# MC21R01_Power.net
KiCad netlist of a schematic drawn in Altium Designer
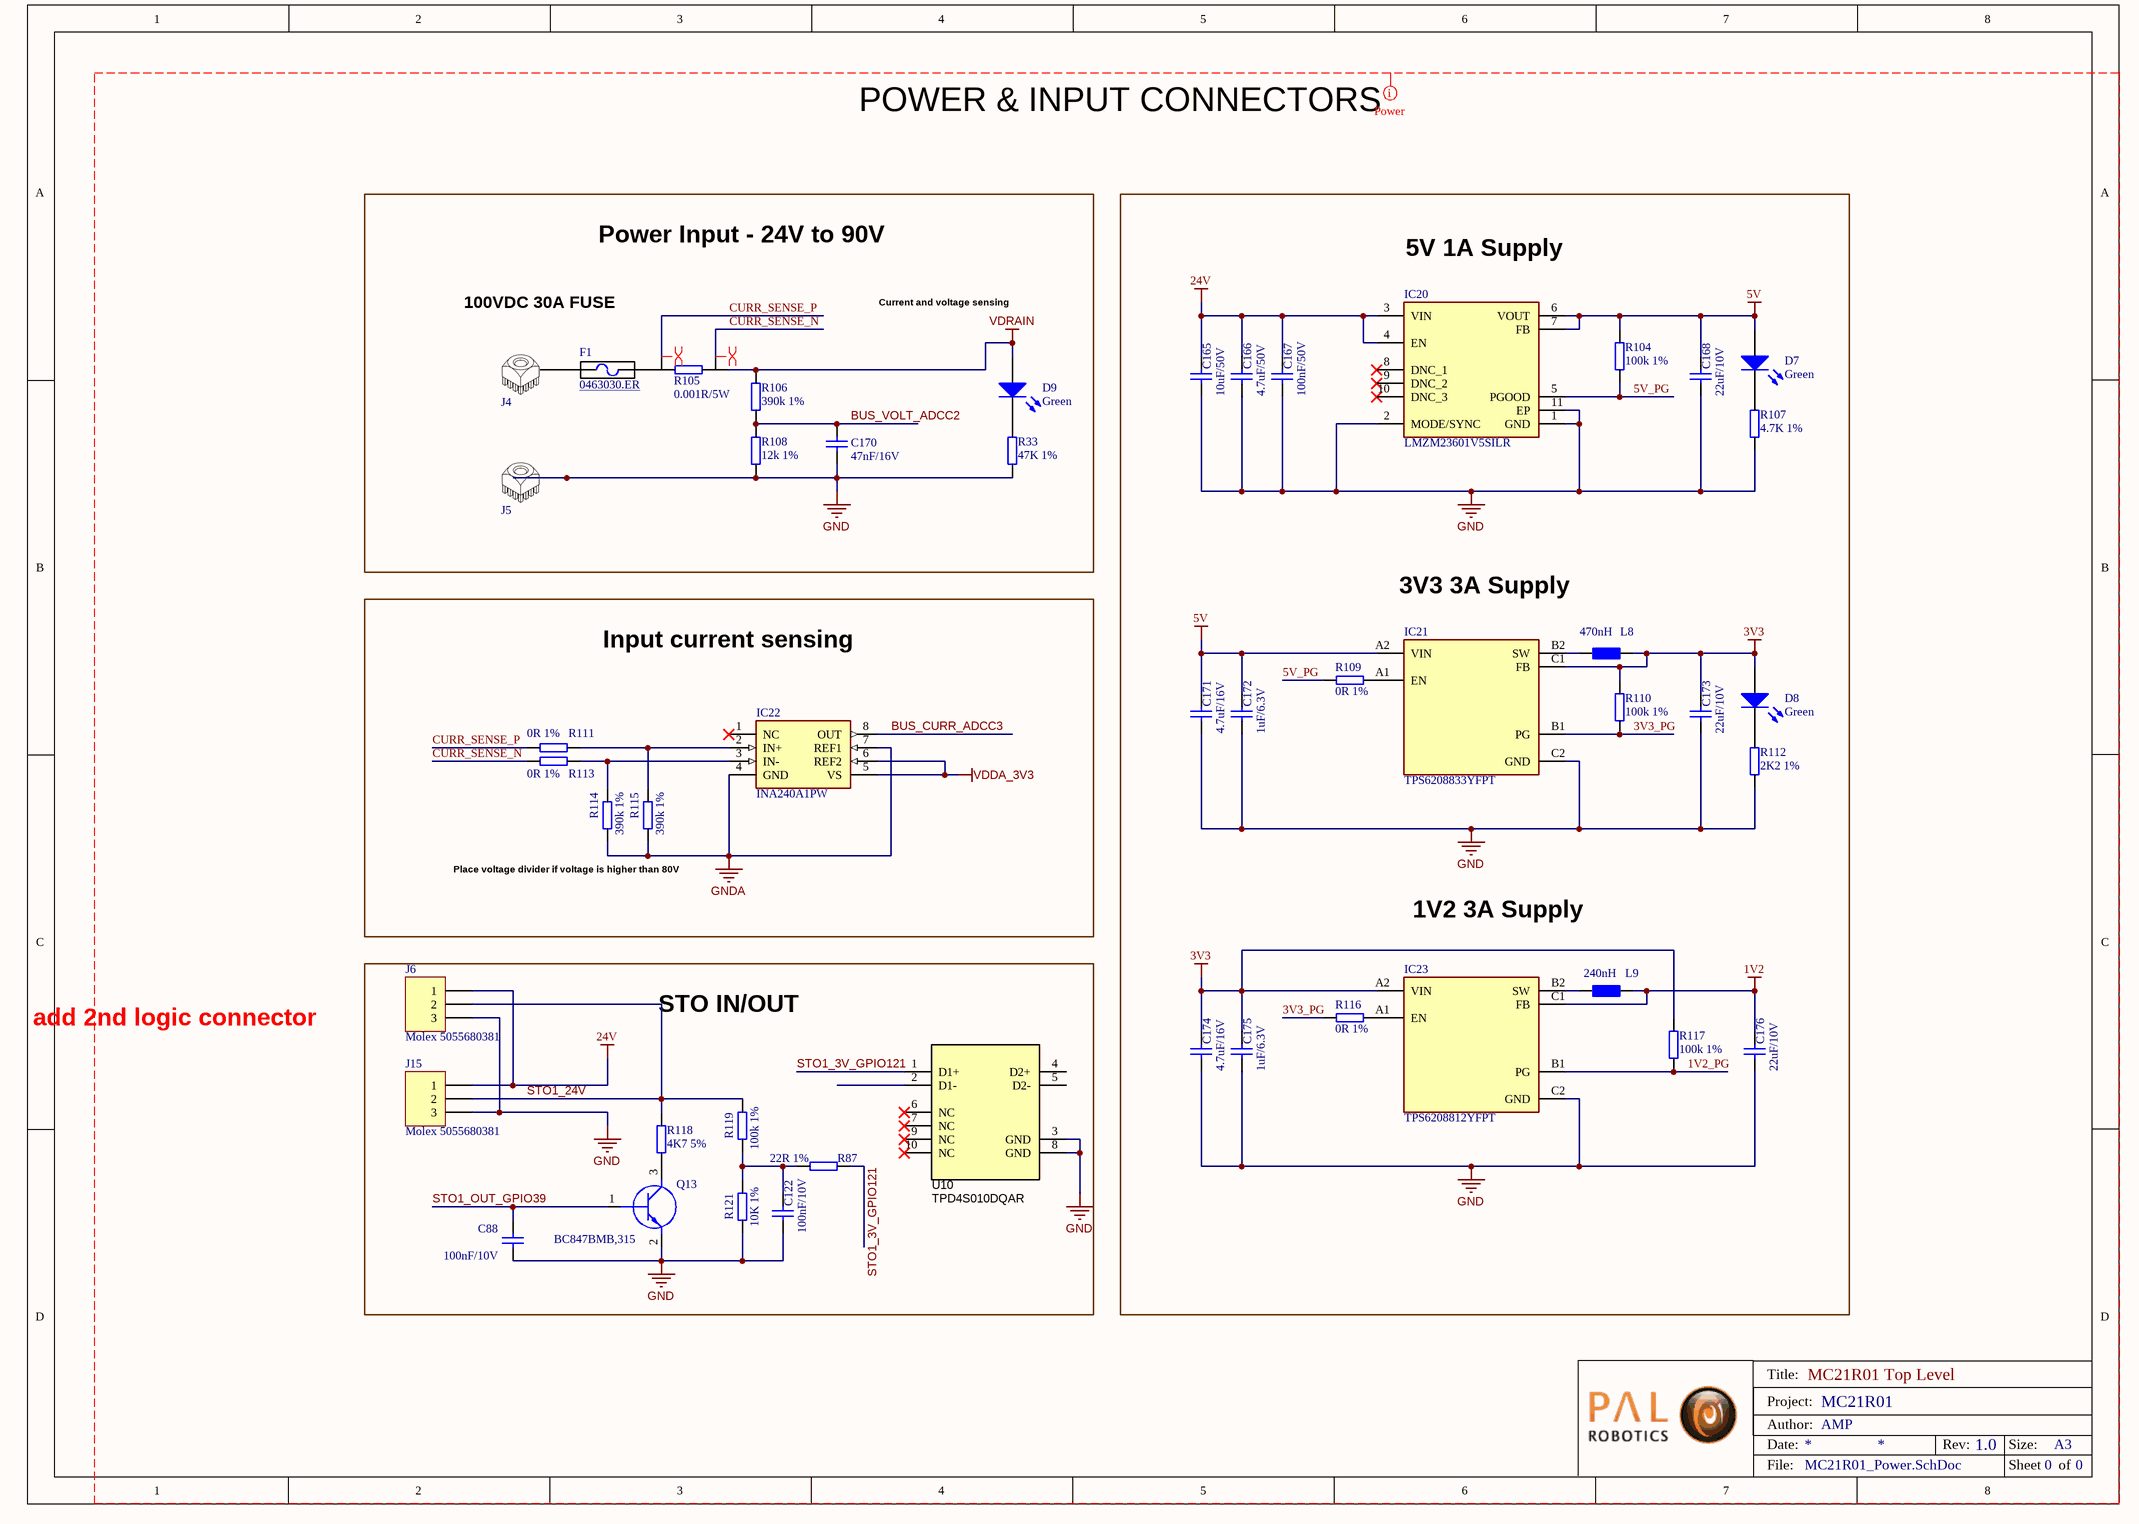
[diagram p0: MC21R01_Power.SchDoc]

(export (version "E")
  (design (tool "Eeschema 10.0.6"))
  (components
    (comp (ref "C88")
      (value "100nF/10V")
      (footprint "PAL_Capacitors:0402 SMD Capacitor")
      (description "100nF/10V 0402 20% Tolerance X5R Multilayer Ceramic Chip Capacitor")
      (fields (field (name "Comment") "100nF/10V 0402 20% X5R"))
      (libsource (lib "PAL_Capacitors") (part "100nF/10V 0402 20% X5R"))
    )
    (comp (ref "C122")
      (value "100nF/10V")
      (footprint "PAL_Capacitors:0402 SMD Capacitor")
      (description "100nF/10V 0402 20% Tolerance X5R Multilayer Ceramic Chip Capacitor")
      (fields (field (name "Comment") "100nF/10V 0402 20% X5R"))
      (libsource (lib "PAL_Capacitors") (part "100nF/10V 0402 20% X5R"))
    )
    (comp (ref "C165")
      (value "10uF/50V")
      (footprint "PAL_Capacitors:1206 SMD Capacitor")
      (description "10 uF 50 V 1206 ±10% Tolerance X5R Multilayer Ceramic Chip Capacitor")
      (fields (field (name "Comment") "10uf/50V 1206 10% X5R"))
      (libsource (lib "PAL_Capacitors") (part "10uF/50V 1206 10% X5R"))
    )
    (comp (ref "C166")
      (value "4.7uF/50V")
      (footprint "PAL_Capacitors:0805 SMD capacitor")
      (description "4.7uF 50 V 0805 ±10% Tolerance X5R Multilayer Ceramic Chip Capacitor")
      (fields (field (name "Comment") "4.7uf/50V 0805 10% X5R"))
      (libsource (lib "PAL_Capacitors") (part "4.7uF/50V 0805 10% X5R"))
    )
    (comp (ref "C167")
      (value "100nF/50V")
      (footprint "PAL_Capacitors:0603 SMD capacitor")
      (description "100 nF 50 V 0603  ±10% Tolerance X7R Multilayer Ceramic Chip Capacitor")
      (fields (field (name "Comment") "100nF/50V 0603 10% X7R"))
      (libsource (lib "PAL_Capacitors") (part "100nF/50V 0603 10% X7R"))
    )
    (comp (ref "C168")
      (value "22uF/10V")
      (footprint "PAL_Capacitors:0603 SMD capacitor")
      (description "22 uF 10 V 0603 ±20% Tolerance X5R Multilayer Ceramic Chip Capacitor")
      (fields (field (name "Comment") "22uF/10V 0603 20% X5R"))
      (libsource (lib "PAL_Capacitors") (part "22uF/10V 0603 20% X5R"))
    )
    (comp (ref "C170")
      (value "47nF/16V")
      (footprint "PAL_Capacitors:0402 SMD Capacitor")
      (description "47nF/16V 0402 10% Tolerance X7R Multilayer Ceramic Chip Capacitor")
      (fields (field (name "Comment") "47nF/16V 0402 10% X7R"))
      (libsource (lib "PAL_Capacitors") (part "47nF/16V 0402 10% X7R"))
    )
    (comp (ref "C171")
      (value "4.7uF/16V")
      (footprint "PAL_Capacitors:0603 SMD capacitor")
      (description "4.7uF/16V 0603 10% Tolerance X5R Multilayer Ceramic Chip Capacitor")
      (fields (field (name "Comment") "4.7uF/16V 0603 10% X5R"))
      (libsource (lib "PAL_Capacitors") (part "4.7uF/16V 0603 10% X5R"))
    )
    (comp (ref "C172")
      (value "1uF/6.3V")
      (footprint "PAL_Capacitors:0402 SMD Capacitor")
      (description "1uF/6.3V 0402 10% Tolerance X5R Multilayer Ceramic Chip Capacitor")
      (fields (field (name "Comment") "1uF/6.3V 0402 10% X5R"))
      (libsource (lib "PAL_Capacitors") (part "1uF/6.3V 0402 10% X5R"))
    )
    (comp (ref "C173")
      (value "22uF/10V")
      (footprint "PAL_Capacitors:0603 SMD capacitor")
      (description "22 uF 10 V 0603 ±20% Tolerance X5R Multilayer Ceramic Chip Capacitor")
      (fields (field (name "Comment") "22uF/10V 0603 20% X5R"))
      (libsource (lib "PAL_Capacitors") (part "22uF/10V 0603 20% X5R"))
    )
    (comp (ref "C174")
      (value "4.7uF/16V")
      (footprint "PAL_Capacitors:0603 SMD capacitor")
      (description "4.7uF/16V 0603 10% Tolerance X5R Multilayer Ceramic Chip Capacitor")
      (fields (field (name "Comment") "4.7uF/16V 0603 10% X5R"))
      (libsource (lib "PAL_Capacitors") (part "4.7uF/16V 0603 10% X5R"))
    )
    (comp (ref "C175")
      (value "1uF/6.3V")
      (footprint "PAL_Capacitors:0402 SMD Capacitor")
      (description "1uF/6.3V 0402 10% Tolerance X5R Multilayer Ceramic Chip Capacitor")
      (fields (field (name "Comment") "1uF/6.3V 0402 10% X5R"))
      (libsource (lib "PAL_Capacitors") (part "1uF/6.3V 0402 10% X5R"))
    )
    (comp (ref "C176")
      (value "22uF/10V")
      (footprint "PAL_Capacitors:0603 SMD capacitor")
      (description "22 uF 10 V 0603 ±20% Tolerance X5R Multilayer Ceramic Chip Capacitor")
      (fields (field (name "Comment") "22uF/10V 0603 20% X5R"))
      (libsource (lib "PAL_Capacitors") (part "22uF/10V 0603 20% X5R"))
    )
    (comp (ref "D7")
      (value "Green")
      (footprint "0402 SMD LED GREEN")
      (description "Low Profile Chip LED, Green")
      (fields (field (name "MANUFACTURER") "ROHM") (field (name "MANUFACTURER PART NUMBER") "SML-P11MTT86R"))
      (libsource (lib "PAL_devices") (part "LED_0402_green"))
    )
    (comp (ref "D8")
      (value "Green")
      (footprint "0402 SMD LED GREEN")
      (description "Low Profile Chip LED, Green")
      (fields (field (name "MANUFACTURER") "ROHM") (field (name "MANUFACTURER PART NUMBER") "SML-P11MTT86R"))
      (libsource (lib "PAL_devices") (part "LED_0402_green"))
    )
    (comp (ref "D9")
      (value "Green")
      (footprint "0402 SMD LED GREEN")
      (description "Low Profile Chip LED, Green")
      (fields (field (name "MANUFACTURER") "ROHM") (field (name "MANUFACTURER PART NUMBER") "SML-P11MTT86R"))
      (libsource (lib "PAL_devices") (part "LED_0402_green"))
    )
    (comp (ref "F1")
      (value "0463030.ER")
      (footprint "0463030.ER")
      (description "LITTELFUSE - 0463030.ER - 100VDC 30A FUSE SMD")
      (libsource (lib "PAL_devices") (part "0463030.ER"))
    )
    (comp (ref "IC20")
      (value "LMZM23601V5SILR")
      (footprint "PAL_devices:LMZM23601V5SILR")
      (description "5V 1A Step-down regulator. 4V to 36V input, 5V fixed output")
      (libsource (lib "PAL_devices") (part "LMZM23601V5SILR"))
    )
    (comp (ref "IC21")
      (value "TPS6208833YFPT")
      (footprint "PAL_IPC-7351B_Footprints:BGA6C40P2X3_80X120X50")
      (description "3.3V 3A Step-Down converter")
      (libsource (lib "PAL_devices") (part "TPS6208833YFPT"))
    )
    (comp (ref "IC22")
      (value "INA240A1PW")
      (footprint "PAL_IPC-7351B_Footprints:SOP65P640X120-8N")
      (description "20V/V current sense amplifier")
      (libsource (lib "PAL_devices") (part "INA240A1PW"))
    )
    (comp (ref "IC23")
      (value "TPS6208812YFPT")
      (footprint "PAL_IPC-7351B_Footprints:BGA6C40P2X3_80X120X50")
      (description "1.2V 3A Step-Down converter")
      (libsource (lib "PAL_devices") (part "TPS6208812YFPT"))
    )
    (comp (ref "J4")
      (value "WE_7461094")
      (footprint "WE_7461094")
      (description "REDCUBE PRESS-FIT with external thread and full plain pin-plate WPSHFU, 130A, M3 screw, 9pins")
      (fields
        (field (name "MANUFACTURER") "WURTH ELEKTRONIK")
        (field (name "MANUFACTURER PART NUMBER") "7461094")
        (field (name "CREATED BY") "Yaiza Montes")
      )
      (libsource (lib "PAL_Wurth_2020") (part "WE_7461094"))
    )
    (comp (ref "J5")
      (value "WE_7461094")
      (footprint "WE_7461094")
      (description "REDCUBE PRESS-FIT with external thread and full plain pin-plate WPSHFU, 130A, M3 screw, 9pins")
      (fields
        (field (name "MANUFACTURER") "WURTH ELEKTRONIK")
        (field (name "MANUFACTURER PART NUMBER") "7461094")
        (field (name "CREATED BY") "Yaiza Montes")
      )
      (libsource (lib "PAL_Wurth_2020") (part "WE_7461094"))
    )
    (comp (ref "J6")
      (value "Molex 5055680381")
      (footprint "Molex 5055680381")
      (fields
        (field (name "MANUFACTURER") "Molex")
        (field (name "MANUFACTURER PART NUMBER") "5055680381")
        (field (name "MATING PART NUMBER") "Molex 5055650301")
        (field (name "CREATED BY") "Yaiza Montes")
      )
      (libsource (lib "PAL_Molex_Micro-Lock_2020") (part "Molex 5055680381"))
    )
    (comp (ref "J15")
      (value "Molex 5055680381")
      (footprint "Molex 5055680381")
      (fields
        (field (name "MANUFACTURER") "Molex")
        (field (name "MANUFACTURER PART NUMBER") "5055680381")
        (field (name "MATING PART NUMBER") "Molex 5055650301")
        (field (name "CREATED BY") "Yaiza Montes")
      )
      (libsource (lib "PAL_Molex_Micro-Lock_2020") (part "Molex 5055680381"))
    )
    (comp (ref "L8")
      (value "470nH")
      (footprint "PAL_Inductors:0603 SMD inductor")
      (description "Inductor, 470nH, 0603 [1608 Metric], 2.6 A, 0.054 ohm, ± 20%")
      (fields (field (name "MPN") "DFE18SANR47MG0L") (field (name "MF") "MURATA"))
      (libsource (lib "PAL_Inductors") (part "470nH/3.2A, 0603 , 2.6 A, 0.054 ohm, ± 20%"))
    )
    (comp (ref "L9")
      (value "240nH")
      (footprint "PAL_Inductors:0603 SMD inductor")
      (description "Inductor, 240nH, 0603 [1608 Metric], 3.2 A, 0.036 ohm, ± 20%")
      (fields (field (name "MPN") "DFE18SANR24ME0L") (field (name "MF") "MURATA"))
      (libsource (lib "PAL_Inductors") (part "240nH/3.2A, 0603 , 3 A, 0.036 ohm, ± 20%"))
    )
    (comp (ref "Q13")
      (value "BC847BMB,315")
      (footprint "PAL_IPC-7351B_Footprints:SOT883B")
      (description "Transistor BJT NPN")
      (fields (field (name "MOUSER PART NUMBER") "771-BC847BMB315"))
      (libsource (lib "PAL_devices") (part "BC847BMB,315"))
    )
    (comp (ref "R33")
      (value "47K 1%")
      (footprint "0402 SMD rESISTOR")
      (description "47K/50V 1% 0402 100mW SMD Resistor")
      (libsource (lib "PAL_Resistors") (part "47K/50V 1% 0402 100mW"))
    )
    (comp (ref "R87")
      (value "22R 1%")
      (footprint "0402 SMD rESISTOR")
      (description "22R/50V 1% 0402 63mW SMD Resistor")
      (libsource (lib "PAL_Resistors") (part "22R/50V 1% 0402 63mW"))
    )
    (comp (ref "R104")
      (value "100k 1%")
      (footprint "0402 SMD rESISTOR")
      (description "100k/50V 1% 0402 100mW SMD Resistor")
      (libsource (lib "PAL_Resistors") (part "100k/50V 1% 0402 100mW"))
    )
    (comp (ref "R105")
      (value "0.001R/5W")
      (footprint "PAL_Resistors:2512 SMD Resistor V2 NETTIE")
      (description "0.001R/5W 1% 2512 shunt SMD Resistor")
      (libsource (lib "PAL_Resistors") (part "0.001R/5W 1% 2512 Shunt"))
    )
    (comp (ref "R106")
      (value "390k 1%")
      (footprint "PAL_Resistors:0603 SMD resistor")
      (description "390k/150V 1% 0603 250mW SMD Resistor")
      (libsource (lib "PAL_Resistors") (part "390k/150V 1% 0603 250mW"))
    )
    (comp (ref "R107")
      (value "4.7K 1%")
      (footprint "0402 SMD rESISTOR")
      (description "4.7K/50V 1% 0402 100mW SMD Resistor")
      (libsource (lib "PAL_Resistors") (part "4.7K/50V 1% 0402 100mW"))
    )
    (comp (ref "R108")
      (value "12k 1%")
      (footprint "PAL_Resistors:0603 SMD resistor")
      (description "12k/150V 1% 0603 250mW SMD Resistor")
      (libsource (lib "PAL_Resistors") (part "12k/150V 1% 0603 250mW"))
    )
    (comp (ref "R109")
      (value "0R 1%")
      (footprint "0402 SMD rESISTOR")
      (description "0R/50V 1% 0402 100mW SMD Resistor")
      (libsource (lib "PAL_Resistors") (part "0R/50V 1% 0402 100mW"))
    )
    (comp (ref "R110")
      (value "100k 1%")
      (footprint "0402 SMD rESISTOR")
      (description "100k/50V 1% 0402 100mW SMD Resistor")
      (libsource (lib "PAL_Resistors") (part "100k/50V 1% 0402 100mW"))
    )
    (comp (ref "R111")
      (value "0R 1%")
      (footprint "0402 SMD rESISTOR")
      (description "0R/100V 1% 0402 63mW SMD Resistor")
      (libsource (lib "PAL_Resistors") (part "0R/100V 1% 0402 63mW"))
    )
    (comp (ref "R112")
      (value "2K2 1%")
      (footprint "0402 SMD rESISTOR")
      (description "2K2/50V 1% 0402 100mW SMD Resistor")
      (libsource (lib "PAL_Resistors") (part "2K2/50V 1% 0402 100mW"))
    )
    (comp (ref "R113")
      (value "0R 1%")
      (footprint "0402 SMD rESISTOR")
      (description "0R/100V 1% 0402 63mW SMD Resistor")
      (libsource (lib "PAL_Resistors") (part "0R/100V 1% 0402 63mW"))
    )
    (comp (ref "R114")
      (value "390k 1%")
      (footprint "PAL_Resistors:0603 SMD resistor")
      (description "390k/150V 1% 0603 250mW SMD Resistor")
      (libsource (lib "PAL_Resistors") (part "390k/150V 1% 0603 250mW"))
    )
    (comp (ref "R115")
      (value "390k 1%")
      (footprint "PAL_Resistors:0603 SMD resistor")
      (description "390k/150V 1% 0603 250mW SMD Resistor")
      (libsource (lib "PAL_Resistors") (part "390k/150V 1% 0603 250mW"))
    )
    (comp (ref "R116")
      (value "0R 1%")
      (footprint "0402 SMD rESISTOR")
      (description "0R/50V 1% 0402 100mW SMD Resistor")
      (libsource (lib "PAL_Resistors") (part "0R/50V 1% 0402 100mW"))
    )
    (comp (ref "R117")
      (value "100k 1%")
      (footprint "0402 SMD rESISTOR")
      (description "100k/50V 1% 0402 100mW SMD Resistor")
      (libsource (lib "PAL_Resistors") (part "100k/50V 1% 0402 100mW"))
    )
    (comp (ref "R118")
      (value "4K7 5%")
      (footprint "PAL_Resistors:0603 SMD resistor")
      (description "4K7/75V 5% 0603 100mW SMD Resistor")
      (libsource (lib "PAL_Resistors") (part "4K7/75V 5% 0603 100mW"))
    )
    (comp (ref "R119")
      (value "100k 1%")
      (footprint "0402 SMD rESISTOR")
      (description "100k/50V 1% 0402 100mW SMD Resistor")
      (libsource (lib "PAL_Resistors") (part "100k/50V 1% 0402 100mW"))
    )
    (comp (ref "R121")
      (value "10K 1%")
      (footprint "0402 SMD rESISTOR")
      (description "10K/50V 1% 0402 100mW SMD Resistor")
      (libsource (lib "PAL_Resistors") (part "10K/50V 1% 0402 100mW"))
    )
    (comp (ref "U10")
      (value "TPD4S010DQAR")
      (footprint "DQA0010A")
      (fields (field (name "MANUFACTURER") "Texas Instruments") (field (name "PARTNUMBER") "TPD4S010DQAR"))
      (libsource (lib "PAL_devices") (part "TPD4S010DQAR"))
    )
  )
  (nets
    (net (code "1") (name "/1V2_PG") (class "Default")
      (node (ref "IC23") (pin "B1") (pinfunction "PG_B1") (pintype "passive"))
      (node (ref "R117") (pin "1") (pinfunction "1_1") (pintype "passive"))
    )
    (net (code "2") (name "/3V3_PG") (class "Default")
      (node (ref "IC21") (pin "B1") (pinfunction "PG_B1") (pintype "passive"))
      (node (ref "R110") (pin "1") (pinfunction "1_1") (pintype "passive"))
      (node (ref "R116") (pin "2") (pinfunction "2_2") (pintype "passive"))
    )
    (net (code "3") (name "/5V_PG") (class "Default")
      (node (ref "IC20") (pin "5") (pinfunction "PGOOD_5") (pintype "passive"))
      (node (ref "R104") (pin "1") (pinfunction "1_1") (pintype "passive"))
      (node (ref "R109") (pin "2") (pinfunction "2_2") (pintype "passive"))
    )
    (net (code "4") (name "/BUS_CURR_ADCC3") (class "Default")
      (node (ref "IC22") (pin "8") (pinfunction "OUT_8") (pintype "output"))
    )
    (net (code "5") (name "/BUS_VOLT_ADCC2") (class "Default")
      (node (ref "C170") (pin "1") (pinfunction "1_1") (pintype "passive"))
      (node (ref "R106") (pin "1") (pinfunction "1_1") (pintype "passive"))
      (node (ref "R108") (pin "2") (pinfunction "2_2") (pintype "passive"))
    )
    (net (code "6") (name "/CURR_SENSE_N") (class "Default")
      (node (ref "R105") (pin "3") (pinfunction "3_3") (pintype "passive"))
      (node (ref "R113") (pin "1") (pinfunction "1_1") (pintype "passive"))
    )
    (net (code "7") (name "/CURR_SENSE_P") (class "Default")
      (node (ref "R105") (pin "4") (pinfunction "4_4") (pintype "passive"))
      (node (ref "R111") (pin "2") (pinfunction "2_2") (pintype "passive"))
    )
    (net (code "8") (name "/STO1_3V_GPIO121") (class "Default")
      (node (ref "R87") (pin "1") (pinfunction "1_1") (pintype "passive"))
      (node (ref "U10") (pin "1") (pinfunction "D1+_1") (pintype "passive"))
    )
    (net (code "9") (name "/STO1_24V") (class "Default")
      (node (ref "J15") (pin "2") (pinfunction "2_2") (pintype "passive"))
      (node (ref "J6") (pin "2") (pinfunction "2_2") (pintype "passive"))
      (node (ref "R118") (pin "2") (pinfunction "2_2") (pintype "passive"))
      (node (ref "R119") (pin "2") (pinfunction "2_2") (pintype "passive"))
    )
    (net (code "10") (name "/STO1_OUT_GPIO39") (class "Default")
      (node (ref "C88") (pin "1") (pinfunction "1_1") (pintype "passive"))
      (node (ref "Q13") (pin "1") (pinfunction "B_1") (pintype "passive"))
    )
    (net (code "11") (name "1V2") (class "Default")
      (node (ref "C176") (pin "1") (pinfunction "1_1") (pintype "passive"))
      (node (ref "IC23") (pin "C1") (pinfunction "FB_C1") (pintype "passive"))
      (node (ref "L9") (pin "1") (pinfunction "1_1") (pintype "passive"))
    )
    (net (code "12") (name "3V3") (class "Default")
      (node (ref "C173") (pin "1") (pinfunction "1_1") (pintype "passive"))
      (node (ref "C174") (pin "1") (pinfunction "1_1") (pintype "passive"))
      (node (ref "C175") (pin "1") (pinfunction "1_1") (pintype "passive"))
      (node (ref "D8") (pin "A") (pinfunction "A_A") (pintype "passive"))
      (node (ref "IC21") (pin "C1") (pinfunction "FB_C1") (pintype "passive"))
      (node (ref "IC23") (pin "A2") (pinfunction "VIN_A2") (pintype "passive"))
      (node (ref "L8") (pin "1") (pinfunction "1_1") (pintype "passive"))
      (node (ref "R110") (pin "2") (pinfunction "2_2") (pintype "passive"))
      (node (ref "R117") (pin "2") (pinfunction "2_2") (pintype "passive"))
    )
    (net (code "13") (name "5V") (class "Default")
      (node (ref "C168") (pin "1") (pinfunction "1_1") (pintype "passive"))
      (node (ref "C171") (pin "1") (pinfunction "1_1") (pintype "passive"))
      (node (ref "C172") (pin "1") (pinfunction "1_1") (pintype "passive"))
      (node (ref "D7") (pin "A") (pinfunction "A_A") (pintype "passive"))
      (node (ref "IC20") (pin "6") (pinfunction "VOUT_6") (pintype "passive"))
      (node (ref "IC20") (pin "7") (pinfunction "FB_7") (pintype "passive"))
      (node (ref "IC21") (pin "A2") (pinfunction "VIN_A2") (pintype "passive"))
      (node (ref "R104") (pin "2") (pinfunction "2_2") (pintype "passive"))
    )
    (net (code "14") (name "24V") (class "Default")
      (node (ref "C165") (pin "1") (pinfunction "1_1") (pintype "passive"))
      (node (ref "C166") (pin "1") (pinfunction "1_1") (pintype "passive"))
      (node (ref "C167") (pin "1") (pinfunction "1_1") (pintype "passive"))
      (node (ref "IC20") (pin "3") (pinfunction "VIN_3") (pintype "passive"))
      (node (ref "IC20") (pin "4") (pinfunction "EN_4") (pintype "passive"))
      (node (ref "J15") (pin "1") (pinfunction "1_1") (pintype "passive"))
      (node (ref "J6") (pin "1") (pinfunction "1_1") (pintype "passive"))
    )
    (net (code "15") (name "GND") (class "Default")
      (node (ref "C122") (pin "2") (pinfunction "2_2") (pintype "passive"))
      (node (ref "C165") (pin "2") (pinfunction "2_2") (pintype "passive"))
      (node (ref "C166") (pin "2") (pinfunction "2_2") (pintype "passive"))
      (node (ref "C167") (pin "2") (pinfunction "2_2") (pintype "passive"))
      (node (ref "C168") (pin "2") (pinfunction "2_2") (pintype "passive"))
      (node (ref "C170") (pin "2") (pinfunction "2_2") (pintype "passive"))
      (node (ref "C171") (pin "2") (pinfunction "2_2") (pintype "passive"))
      (node (ref "C172") (pin "2") (pinfunction "2_2") (pintype "passive"))
      (node (ref "C173") (pin "2") (pinfunction "2_2") (pintype "passive"))
      (node (ref "C174") (pin "2") (pinfunction "2_2") (pintype "passive"))
      (node (ref "C175") (pin "2") (pinfunction "2_2") (pintype "passive"))
      (node (ref "C176") (pin "2") (pinfunction "2_2") (pintype "passive"))
      (node (ref "C88") (pin "2") (pinfunction "2_2") (pintype "passive"))
      (node (ref "IC20") (pin "1") (pinfunction "GND_1") (pintype "passive"))
      (node (ref "IC20") (pin "11") (pinfunction "EP_11") (pintype "passive"))
      (node (ref "IC20") (pin "2") (pinfunction "MODE/SYNC_2") (pintype "passive"))
      (node (ref "IC21") (pin "C2") (pinfunction "GND_C2") (pintype "passive"))
      (node (ref "IC23") (pin "C2") (pinfunction "GND_C2") (pintype "passive"))
      (node (ref "J15") (pin "3") (pinfunction "3_3") (pintype "passive"))
      (node (ref "J5") (pin "1") (pinfunction "1_1") (pintype "passive"))
      (node (ref "J6") (pin "3") (pinfunction "3_3") (pintype "passive"))
      (node (ref "Q13") (pin "2") (pinfunction "E_2") (pintype "passive"))
      (node (ref "R107") (pin "1") (pinfunction "1_1") (pintype "passive"))
      (node (ref "R108") (pin "1") (pinfunction "1_1") (pintype "passive"))
      (node (ref "R112") (pin "1") (pinfunction "1_1") (pintype "passive"))
      (node (ref "R121") (pin "1") (pinfunction "1_1") (pintype "passive"))
      (node (ref "R33") (pin "1") (pinfunction "1_1") (pintype "passive"))
      (node (ref "U10") (pin "3") (pinfunction "GND_3") (pintype "power_in"))
      (node (ref "U10") (pin "8") (pinfunction "GND_8") (pintype "power_in"))
    )
    (net (code "16") (name "GNDA") (class "Default")
      (node (ref "IC22") (pin "4") (pinfunction "GND_4") (pintype "power_in"))
      (node (ref "IC22") (pin "7") (pinfunction "REF1_7") (pintype "input"))
      (node (ref "R114") (pin "1") (pinfunction "1_1") (pintype "passive"))
      (node (ref "R115") (pin "1") (pinfunction "1_1") (pintype "passive"))
    )
    (net (code "17") (name "Net-(C122-Pad1)") (class "Default")
      (node (ref "C122") (pin "1") (pinfunction "1_1") (pintype "passive"))
      (node (ref "R119") (pin "1") (pinfunction "1_1") (pintype "passive"))
      (node (ref "R121") (pin "2") (pinfunction "2_2") (pintype "passive"))
      (node (ref "R87") (pin "2") (pinfunction "2_2") (pintype "passive"))
    )
    (net (code "18") (name "Net-(D7-PadK)") (class "Default")
      (node (ref "D7") (pin "K") (pinfunction "K_K") (pintype "passive"))
      (node (ref "R107") (pin "2") (pinfunction "2_2") (pintype "passive"))
    )
    (net (code "19") (name "Net-(D8-PadK)") (class "Default")
      (node (ref "D8") (pin "K") (pinfunction "K_K") (pintype "passive"))
      (node (ref "R112") (pin "2") (pinfunction "2_2") (pintype "passive"))
    )
    (net (code "20") (name "Net-(D9-PadK)") (class "Default")
      (node (ref "D9") (pin "K") (pinfunction "K_K") (pintype "passive"))
      (node (ref "R33") (pin "2") (pinfunction "2_2") (pintype "passive"))
    )
    (net (code "21") (name "Net-(F1-Pad1)") (class "Default")
      (node (ref "F1") (pin "1") (pinfunction "1_1") (pintype "passive"))
      (node (ref "J4") (pin "1") (pinfunction "1_1") (pintype "passive"))
    )
    (net (code "22") (name "Net-(F1-Pad2)") (class "Default")
      (node (ref "F1") (pin "2") (pinfunction "2_2") (pintype "passive"))
      (node (ref "R105") (pin "2") (pinfunction "2_2") (pintype "passive"))
    )
    (net (code "23") (name "Net-(IC21-EN)") (class "Default")
      (node (ref "IC21") (pin "A1") (pinfunction "EN_A1") (pintype "passive"))
      (node (ref "R109") (pin "1") (pinfunction "1_1") (pintype "passive"))
    )
    (net (code "24") (name "Net-(IC21-SW)") (class "Default")
      (node (ref "IC21") (pin "B2") (pinfunction "SW_B2") (pintype "passive"))
      (node (ref "L8") (pin "2") (pinfunction "2_2") (pintype "passive"))
    )
    (net (code "25") (name "Net-(IC22-IN+)") (class "Default")
      (node (ref "IC22") (pin "2") (pinfunction "IN+_2") (pintype "input"))
      (node (ref "R111") (pin "1") (pinfunction "1_1") (pintype "passive"))
      (node (ref "R115") (pin "2") (pinfunction "2_2") (pintype "passive"))
    )
    (net (code "26") (name "Net-(IC22-IN-)") (class "Default")
      (node (ref "IC22") (pin "3") (pinfunction "IN-_3") (pintype "input"))
      (node (ref "R113") (pin "2") (pinfunction "2_2") (pintype "passive"))
      (node (ref "R114") (pin "2") (pinfunction "2_2") (pintype "passive"))
    )
    (net (code "27") (name "Net-(IC23-EN)") (class "Default")
      (node (ref "IC23") (pin "A1") (pinfunction "EN_A1") (pintype "passive"))
      (node (ref "R116") (pin "1") (pinfunction "1_1") (pintype "passive"))
    )
    (net (code "28") (name "Net-(IC23-SW)") (class "Default")
      (node (ref "IC23") (pin "B2") (pinfunction "SW_B2") (pintype "passive"))
      (node (ref "L9") (pin "2") (pinfunction "2_2") (pintype "passive"))
    )
    (net (code "29") (name "Net-(Q13-C)") (class "Default")
      (node (ref "Q13") (pin "3") (pinfunction "C_3") (pintype "passive"))
      (node (ref "R118") (pin "1") (pinfunction "1_1") (pintype "passive"))
    )
    (net (code "30") (name "VDDA_3V3") (class "Default")
      (node (ref "IC22") (pin "5") (pinfunction "VS_5") (pintype "power_in"))
      (node (ref "IC22") (pin "6") (pinfunction "REF2_6") (pintype "input"))
    )
    (net (code "31") (name "VDRAIN") (class "Default")
      (node (ref "D9") (pin "A") (pinfunction "A_A") (pintype "passive"))
      (node (ref "R105") (pin "1") (pinfunction "1_1") (pintype "passive"))
      (node (ref "R106") (pin "2") (pinfunction "2_2") (pintype "passive"))
    )
    (net (code "32") (name "unconnected-(IC20-DNC_1-Pad8)") (class "Default")
      (node (ref "IC20") (pin "8") (pinfunction "DNC_1_8") (pintype "passive+no_connect"))
    )
    (net (code "33") (name "unconnected-(IC20-DNC_2-Pad9)") (class "Default")
      (node (ref "IC20") (pin "9") (pinfunction "DNC_2_9") (pintype "passive+no_connect"))
    )
    (net (code "34") (name "unconnected-(IC20-DNC_3-Pad10)") (class "Default")
      (node (ref "IC20") (pin "10") (pinfunction "DNC_3_10") (pintype "passive+no_connect"))
    )
    (net (code "35") (name "unconnected-(IC22-NC-Pad1)") (class "Default")
      (node (ref "IC22") (pin "1") (pinfunction "NC_1") (pintype "passive+no_connect"))
    )
    (net (code "36") (name "unconnected-(U10-D1--Pad2)") (class "Default")
      (node (ref "U10") (pin "2") (pinfunction "D1-_2") (pintype "passive"))
    )
    (net (code "37") (name "unconnected-(U10-D2+-Pad4)") (class "Default")
      (node (ref "U10") (pin "4") (pinfunction "D2+_4") (pintype "passive"))
    )
    (net (code "38") (name "unconnected-(U10-D2--Pad5)") (class "Default")
      (node (ref "U10") (pin "5") (pinfunction "D2-_5") (pintype "passive"))
    )
    (net (code "39") (name "unconnected-(U10-NC-Pad6)") (class "Default")
      (node (ref "U10") (pin "6") (pinfunction "NC_6") (pintype "passive+no_connect"))
    )
    (net (code "40") (name "unconnected-(U10-NC-Pad7)") (class "Default")
      (node (ref "U10") (pin "7") (pinfunction "NC_7") (pintype "passive+no_connect"))
    )
    (net (code "41") (name "unconnected-(U10-NC-Pad9)") (class "Default")
      (node (ref "U10") (pin "9") (pinfunction "NC_9") (pintype "passive+no_connect"))
    )
    (net (code "42") (name "unconnected-(U10-NC-Pad10)") (class "Default")
      (node (ref "U10") (pin "10") (pinfunction "NC_10") (pintype "passive+no_connect"))
    )
  )
)
